# cover_pcb_2.net
KiCad netlist of a schematic drawn in EAGLE
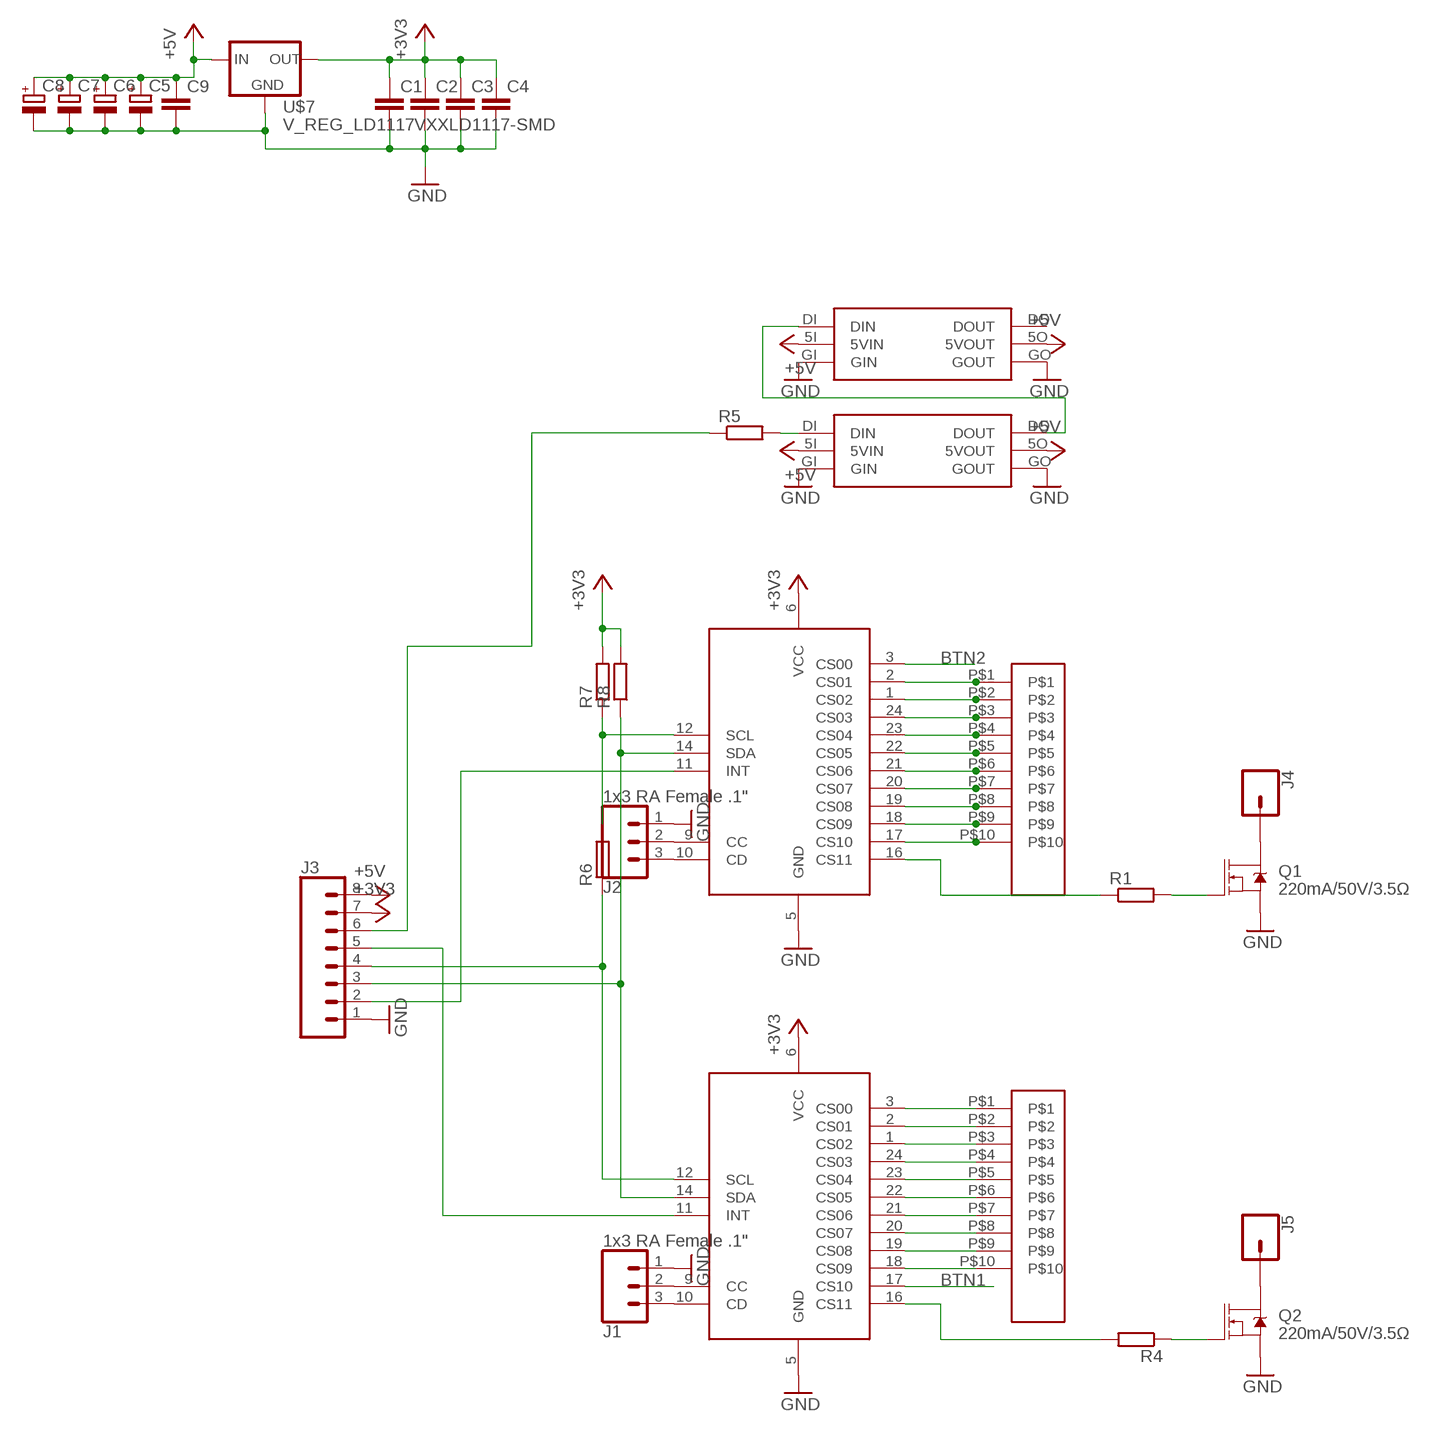
[diagram p0: schematic, sheet 1]
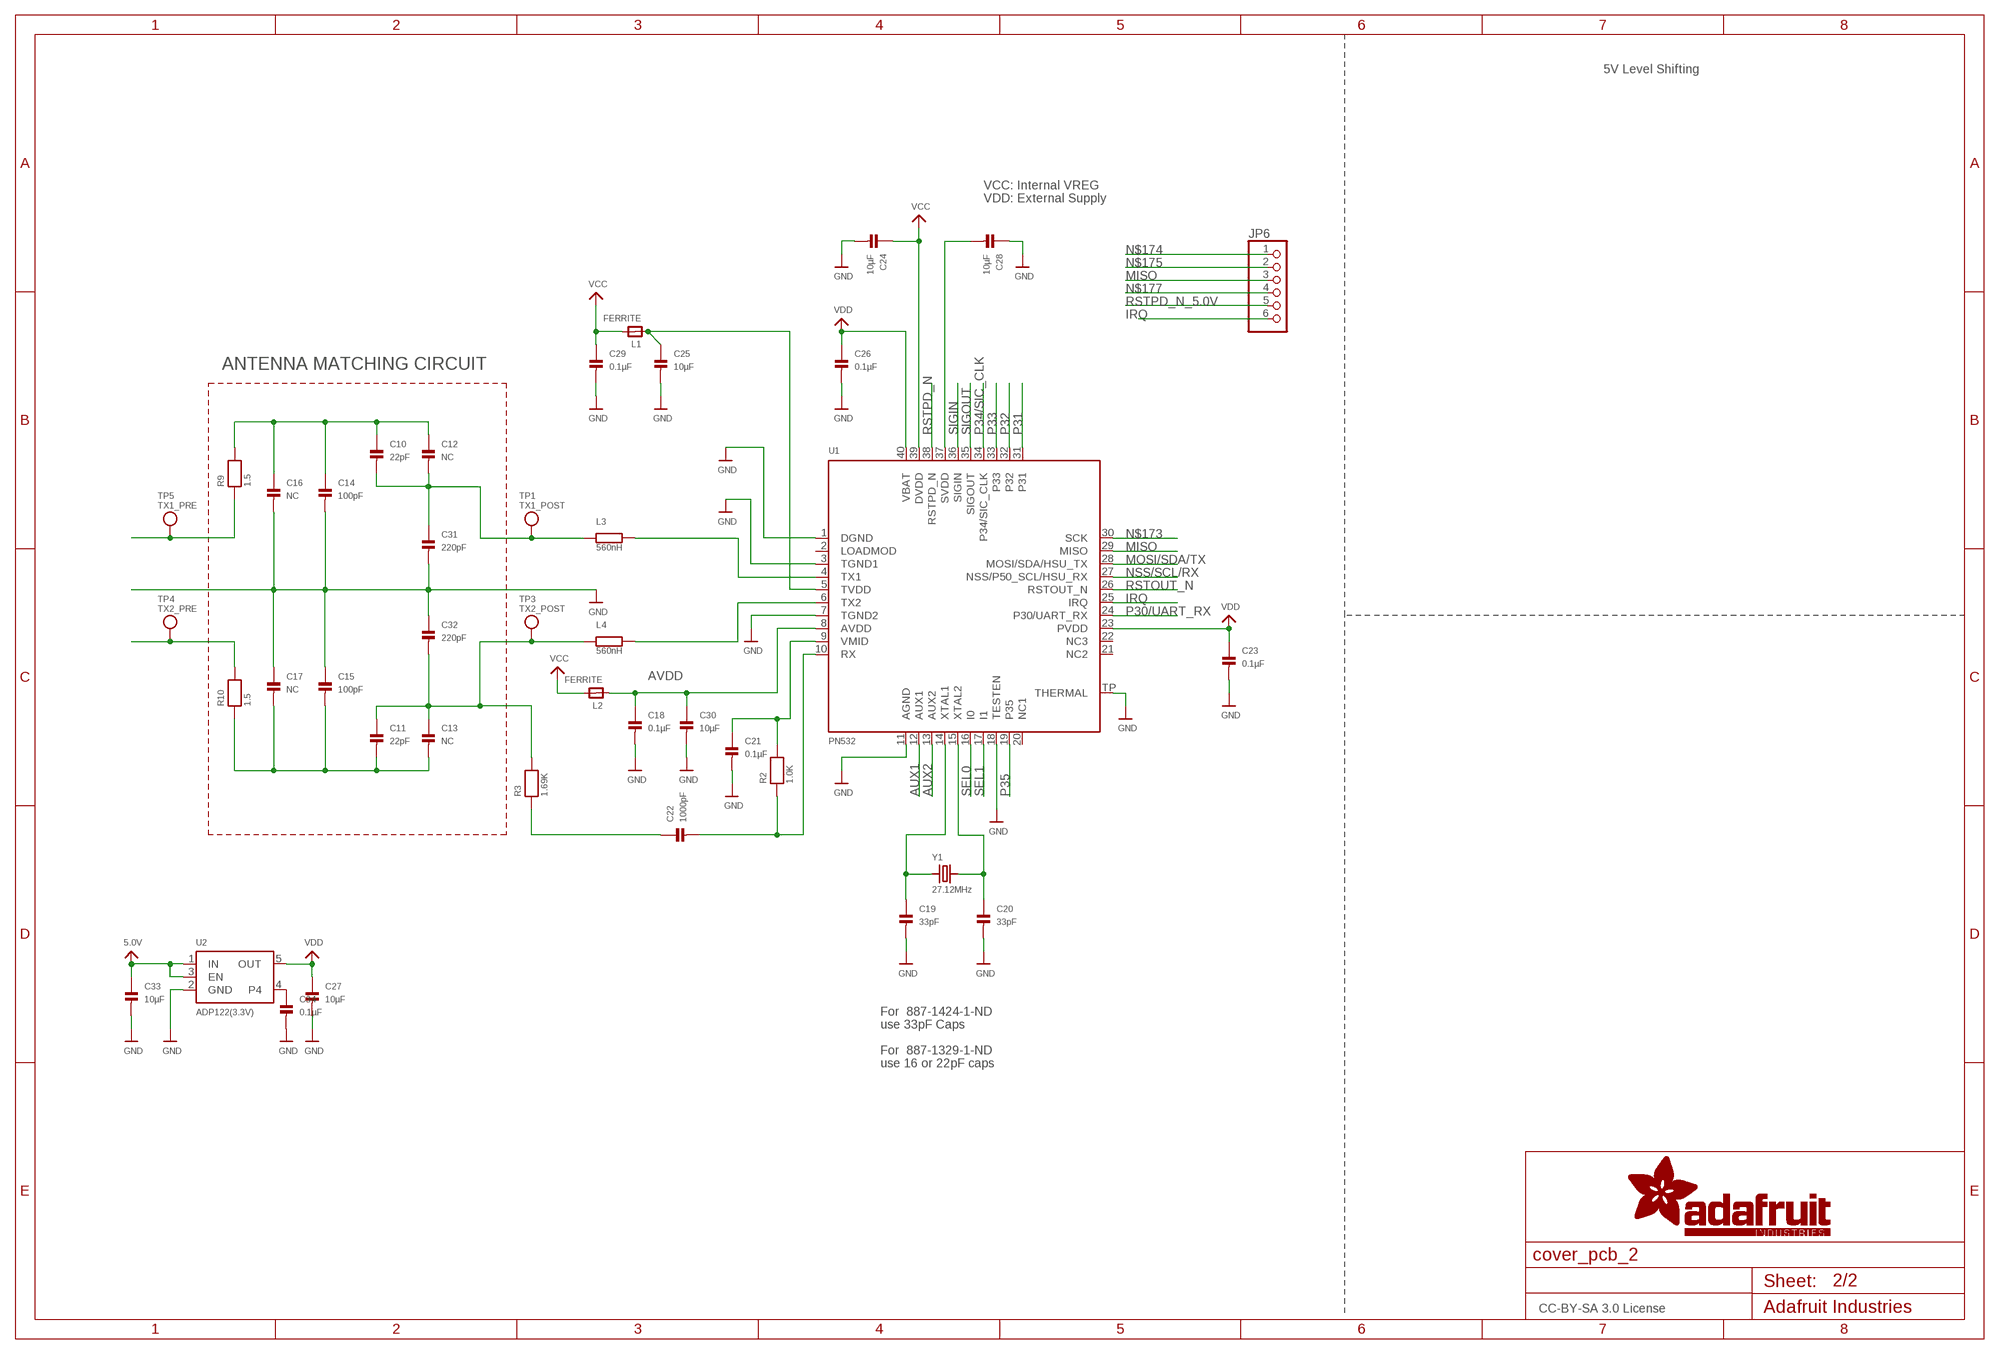
[diagram p1: schematic, sheet 2]

(export (version "E")
  (design (tool "Eeschema 10.0.6"))
  (components
    (comp (ref "C10")
      (value "22pF")
      (footprint "eagle-import:0805")
      (libsource (lib "eagle-import") (part "CAP_CERAMIC0805"))
    )
    (comp (ref "C11")
      (value "22pF")
      (footprint "eagle-import:0805")
      (libsource (lib "eagle-import") (part "CAP_CERAMIC0805"))
    )
    (comp (ref "C12")
      (value "NC")
      (footprint "eagle-import:0805")
      (libsource (lib "eagle-import") (part "CAP_CERAMIC0805"))
    )
    (comp (ref "C13")
      (value "NC")
      (footprint "eagle-import:0805")
      (libsource (lib "eagle-import") (part "CAP_CERAMIC0805"))
    )
    (comp (ref "C14")
      (value "100pF")
      (footprint "eagle-import:0805")
      (libsource (lib "eagle-import") (part "CAP_CERAMIC0805"))
    )
    (comp (ref "C15")
      (value "100pF")
      (footprint "eagle-import:0805")
      (libsource (lib "eagle-import") (part "CAP_CERAMIC0805"))
    )
    (comp (ref "C16")
      (value "NC")
      (footprint "eagle-import:0805")
      (libsource (lib "eagle-import") (part "CAP_CERAMIC0805"))
    )
    (comp (ref "C17")
      (value "NC")
      (footprint "eagle-import:0805")
      (libsource (lib "eagle-import") (part "CAP_CERAMIC0805"))
    )
    (comp (ref "C18")
      (value "0.1µF")
      (footprint "eagle-import:0805")
      (libsource (lib "eagle-import") (part "CAP_CERAMIC0805"))
    )
    (comp (ref "C19")
      (value "33pF")
      (footprint "eagle-import:0805")
      (libsource (lib "eagle-import") (part "CAP_CERAMIC0805"))
    )
    (comp (ref "C20")
      (value "33pF")
      (footprint "eagle-import:0805")
      (libsource (lib "eagle-import") (part "CAP_CERAMIC0805"))
    )
    (comp (ref "C21")
      (value "0.1µF")
      (footprint "eagle-import:0805")
      (libsource (lib "eagle-import") (part "CAP_CERAMIC0805"))
    )
    (comp (ref "C22")
      (value "1000pF")
      (footprint "eagle-import:0805")
      (libsource (lib "eagle-import") (part "CAP_CERAMIC0805"))
    )
    (comp (ref "C23")
      (value "0.1µF")
      (footprint "eagle-import:0805")
      (libsource (lib "eagle-import") (part "CAP_CERAMIC0805"))
    )
    (comp (ref "C24")
      (value "10µF")
      (footprint "eagle-import:0805")
      (libsource (lib "eagle-import") (part "CAP_CERAMIC0805"))
    )
    (comp (ref "C25")
      (value "10µF")
      (footprint "eagle-import:0805")
      (libsource (lib "eagle-import") (part "CAP_CERAMIC0805"))
    )
    (comp (ref "C26")
      (value "0.1µF")
      (footprint "eagle-import:0805")
      (libsource (lib "eagle-import") (part "CAP_CERAMIC0805"))
    )
    (comp (ref "C27")
      (value "10µF")
      (footprint "eagle-import:0805")
      (libsource (lib "eagle-import") (part "CAP_CERAMIC0805"))
    )
    (comp (ref "C28")
      (value "10µF")
      (footprint "eagle-import:0805")
      (libsource (lib "eagle-import") (part "CAP_CERAMIC0805"))
    )
    (comp (ref "C29")
      (value "0.1µF")
      (footprint "eagle-import:0805")
      (libsource (lib "eagle-import") (part "CAP_CERAMIC0805"))
    )
    (comp (ref "C30")
      (value "10µF")
      (footprint "eagle-import:0805")
      (libsource (lib "eagle-import") (part "CAP_CERAMIC0805"))
    )
    (comp (ref "C31")
      (value "220pF")
      (footprint "eagle-import:0805")
      (libsource (lib "eagle-import") (part "CAP_CERAMIC0805"))
    )
    (comp (ref "C32")
      (value "220pF")
      (footprint "eagle-import:0805")
      (libsource (lib "eagle-import") (part "CAP_CERAMIC0805"))
    )
    (comp (ref "C33")
      (value "10µF")
      (footprint "eagle-import:0805")
      (libsource (lib "eagle-import") (part "CAP_CERAMIC0805"))
    )
    (comp (ref "C34")
      (value "0.1µF")
      (footprint "eagle-import:0805")
      (libsource (lib "eagle-import") (part "CAP_CERAMIC0805"))
    )
    (comp (ref "JP6")
      (value "PINHD-1X6B")
      (footprint "eagle-import:1X06-BIG")
      (libsource (lib "eagle-import") (part "PINHD-1X6B"))
    )
    (comp (ref "L1")
      (value "FERRITE")
      (footprint "eagle-import:0805")
      (libsource (lib "eagle-import") (part "FERRITE0805"))
    )
    (comp (ref "L2")
      (value "FERRITE")
      (footprint "eagle-import:0805")
      (libsource (lib "eagle-import") (part "FERRITE0805"))
    )
    (comp (ref "L3")
      (value "560nH")
      (footprint "eagle-import:R1206")
      (libsource (lib "eagle-import") (part "R-EU_R1206"))
    )
    (comp (ref "L4")
      (value "560nH")
      (footprint "eagle-import:R1206")
      (libsource (lib "eagle-import") (part "R-EU_R1206"))
    )
    (comp (ref "R2")
      (value "1.0K")
      (footprint "eagle-import:0805")
      (libsource (lib "eagle-import") (part "RESISTOR0805"))
    )
    (comp (ref "R3")
      (value "1.69K")
      (footprint "eagle-import:0805")
      (libsource (lib "eagle-import") (part "RESISTOR0805"))
    )
    (comp (ref "R9")
      (value "1.5")
      (footprint "eagle-import:0805")
      (libsource (lib "eagle-import") (part "RESISTOR0805"))
    )
    (comp (ref "R10")
      (value "1.5")
      (footprint "eagle-import:0805")
      (libsource (lib "eagle-import") (part "RESISTOR0805"))
    )
    (comp (ref "TP1")
      (value "TX1_POST")
      (footprint "eagle-import:TESTPOINT_PAD_2MM")
      (libsource (lib "eagle-import") (part "TESTPOINTPAD"))
    )
    (comp (ref "TP3")
      (value "TX2_POST")
      (footprint "eagle-import:TESTPOINT_PAD_2MM")
      (libsource (lib "eagle-import") (part "TESTPOINTPAD"))
    )
    (comp (ref "TP4")
      (value "TX2_PRE")
      (footprint "eagle-import:TESTPOINT_PAD_2MM")
      (libsource (lib "eagle-import") (part "TESTPOINTPAD"))
    )
    (comp (ref "TP5")
      (value "TX1_PRE")
      (footprint "eagle-import:TESTPOINT_PAD_2MM")
      (libsource (lib "eagle-import") (part "TESTPOINTPAD"))
    )
    (comp (ref "U1")
      (value "PN532")
      (footprint "eagle-import:HVQFN40-6X6")
      (libsource (lib "eagle-import") (part "PN532"))
    )
    (comp (ref "U2")
      (value "ADP122(3.3V)")
      (footprint "eagle-import:SOT23-5")
      (libsource (lib "eagle-import") (part "VREG_SOT23-5"))
    )
    (comp (ref "Y1")
      (value "27.12MHz")
      (footprint "eagle-import:CRYSTAL_3.2X2.5")
      (libsource (lib "eagle-import") (part "CRYSTAL3.2X2.5"))
    )
    (comp (ref "C1")
      (value "C-EUC0805K")
      (footprint "eagle-import:C0805K")
      (libsource (lib "eagle-import") (part "C-EUC0805K"))
    )
    (comp (ref "C2")
      (value "C-EUC0805K")
      (footprint "eagle-import:C0805K")
      (libsource (lib "eagle-import") (part "C-EUC0805K"))
    )
    (comp (ref "C3")
      (value "C-EUC0805K")
      (footprint "eagle-import:C0805K")
      (libsource (lib "eagle-import") (part "C-EUC0805K"))
    )
    (comp (ref "C4")
      (value "C-EUC0805K")
      (footprint "eagle-import:C0805K")
      (libsource (lib "eagle-import") (part "C-EUC0805K"))
    )
    (comp (ref "C5")
      (value "CPOL-EUSMCD")
      (footprint "eagle-import:SMC_D")
      (libsource (lib "eagle-import") (part "CPOL-EUSMCD"))
    )
    (comp (ref "C6")
      (value "CPOL-EUSMCD")
      (footprint "eagle-import:SMC_D")
      (libsource (lib "eagle-import") (part "CPOL-EUSMCD"))
    )
    (comp (ref "C7")
      (value "CPOL-EUSMCD")
      (footprint "eagle-import:SMC_D")
      (libsource (lib "eagle-import") (part "CPOL-EUSMCD"))
    )
    (comp (ref "C8")
      (value "CPOL-EUSMCD")
      (footprint "eagle-import:SMC_D")
      (libsource (lib "eagle-import") (part "CPOL-EUSMCD"))
    )
    (comp (ref "C9")
      (value "C-EUC0805K")
      (footprint "eagle-import:C0805K")
      (libsource (lib "eagle-import") (part "C-EUC0805K"))
    )
    (comp (ref "J1")
      (value "1x3 RA Female .1\"")
      (footprint "eagle-import:1X03_SMD_RA_FEMALE")
      (libsource (lib "eagle-import") (part "CONN_03SMD_RA_FEMALE"))
    )
    (comp (ref "J2")
      (value "1x3 RA Female .1\"")
      (footprint "eagle-import:1X03_SMD_RA_FEMALE")
      (libsource (lib "eagle-import") (part "CONN_03SMD_RA_FEMALE"))
    )
    (comp (ref "J3")
      (value "CONN_08SMD-MALE")
      (footprint "eagle-import:1X08_SMD_MALE")
      (libsource (lib "eagle-import") (part "CONN_08SMD-MALE"))
    )
    (comp (ref "J4")
      (value "CONN_01SPRING-CONN")
      (footprint "eagle-import:SPRING-CONNECTOR")
      (libsource (lib "eagle-import") (part "CONN_01SPRING-CONN"))
    )
    (comp (ref "J5")
      (value "CONN_01SPRING-CONN")
      (footprint "eagle-import:SPRING-CONNECTOR")
      (libsource (lib "eagle-import") (part "CONN_01SPRING-CONN"))
    )
    (comp (ref "Q1")
      (value "220mA/50V/3.5Ω")
      (footprint "eagle-import:SOT23-3")
      (libsource (lib "eagle-import") (part "MOSFET-NCH-BSS138"))
    )
    (comp (ref "Q2")
      (value "220mA/50V/3.5Ω")
      (footprint "eagle-import:SOT23-3")
      (libsource (lib "eagle-import") (part "MOSFET-NCH-BSS138"))
    )
    (comp (ref "R1")
      (value "R-EU_R0805")
      (footprint "eagle-import:R0805")
      (libsource (lib "eagle-import") (part "R-EU_R0805"))
    )
    (comp (ref "R4")
      (value "R-EU_R0805")
      (footprint "eagle-import:R0805")
      (libsource (lib "eagle-import") (part "R-EU_R0805"))
    )
    (comp (ref "R5")
      (value "R-EU_R0805")
      (footprint "eagle-import:R0805")
      (libsource (lib "eagle-import") (part "R-EU_R0805"))
    )
    (comp (ref "R6")
      (value "R-EU_R0805")
      (footprint "eagle-import:R0805")
      (libsource (lib "eagle-import") (part "R-EU_R0805"))
    )
    (comp (ref "R7")
      (value "R-EU_R0805")
      (footprint "eagle-import:R0805")
      (libsource (lib "eagle-import") (part "R-EU_R0805"))
    )
    (comp (ref "R8")
      (value "R-EU_R0805")
      (footprint "eagle-import:R0805")
      (libsource (lib "eagle-import") (part "R-EU_R0805"))
    )
    (comp (ref "U$1")
      (value "RGB6LED")
      (footprint "eagle-import:RGB6LED")
      (libsource (lib "eagle-import") (part "RGB6LED"))
    )
    (comp (ref "U$2")
      (value "RGB6LED")
      (footprint "eagle-import:RGB6LED")
      (libsource (lib "eagle-import") (part "RGB6LED"))
    )
    (comp (ref "U$3")
      (value "TOUCH10")
      (footprint "eagle-import:TOUCH10CM")
      (libsource (lib "eagle-import") (part "TOUCH10"))
    )
    (comp (ref "U$4")
      (value "TOUCH10")
      (footprint "eagle-import:TOUCH10CM")
      (libsource (lib "eagle-import") (part "TOUCH10"))
    )
    (comp (ref "U$5")
      (value "CP112S")
      (footprint "eagle-import:QSOP24")
      (libsource (lib "eagle-import") (part "CP112S"))
    )
    (comp (ref "U$6")
      (value "CP112S")
      (footprint "eagle-import:QSOP24")
      (libsource (lib "eagle-import") (part "CP112S"))
    )
    (comp (ref "U$7")
      (value "V_REG_LD1117VXXLD1117-SMD")
      (footprint "eagle-import:SOT223")
      (libsource (lib "eagle-import") (part "V_REG_LD1117VXXLD1117-SMD"))
    )
  )
  (nets
    (net (code "1") (name "+3V3") (class "Default")
      (node (ref "C1") (pin "1") (pinfunction "1_1") (pintype "passive"))
      (node (ref "C2") (pin "1") (pinfunction "1_1") (pintype "passive"))
      (node (ref "C3") (pin "1") (pinfunction "1_1") (pintype "passive"))
      (node (ref "C4") (pin "1") (pinfunction "1_1") (pintype "passive"))
      (node (ref "J3") (pin "7") (pinfunction "7_7") (pintype "passive"))
      (node (ref "R7") (pin "2") (pinfunction "2_2") (pintype "passive"))
      (node (ref "R8") (pin "2") (pinfunction "2_2") (pintype "passive"))
      (node (ref "U$5") (pin "6") (pinfunction "VCC_6") (pintype "bidirectional"))
      (node (ref "U$6") (pin "6") (pinfunction "VCC_6") (pintype "bidirectional"))
      (node (ref "U$7") (pin "2") (pinfunction "OUT_2") (pintype "passive"))
    )
    (net (code "2") (name "+5V") (class "Default")
      (node (ref "C5") (pin "+") (pinfunction "+_+") (pintype "passive"))
      (node (ref "C6") (pin "+") (pinfunction "+_+") (pintype "passive"))
      (node (ref "C7") (pin "+") (pinfunction "+_+") (pintype "passive"))
      (node (ref "C8") (pin "+") (pinfunction "+_+") (pintype "passive"))
      (node (ref "C9") (pin "1") (pinfunction "1_1") (pintype "passive"))
      (node (ref "J3") (pin "8") (pinfunction "8_8") (pintype "passive"))
      (node (ref "U$1") (pin "5I") (pinfunction "5VIN_5I") (pintype "bidirectional"))
      (node (ref "U$1") (pin "5O") (pinfunction "5VOUT_5O") (pintype "bidirectional"))
      (node (ref "U$2") (pin "5I") (pinfunction "5VIN_5I") (pintype "bidirectional"))
      (node (ref "U$2") (pin "5O") (pinfunction "5VOUT_5O") (pintype "bidirectional"))
      (node (ref "U$7") (pin "3") (pinfunction "IN_3") (pintype "input"))
    )
    (net (code "3") (name "5.0V") (class "Default")
      (node (ref "C33") (pin "1") (pinfunction "P$1_1") (pintype "passive"))
      (node (ref "U2") (pin "1") (pinfunction "IN_1") (pintype "bidirectional"))
      (node (ref "U2") (pin "3") (pinfunction "EN_3") (pintype "bidirectional"))
    )
    (net (code "4") (name "AUX1") (class "Default")
      (node (ref "U1") (pin "12") (pinfunction "AUX1_12") (pintype "bidirectional"))
    )
    (net (code "5") (name "AUX2") (class "Default")
      (node (ref "U1") (pin "13") (pinfunction "AUX2_13") (pintype "bidirectional"))
    )
    (net (code "6") (name "AVDD") (class "Default")
      (node (ref "C18") (pin "1") (pinfunction "P$1_1") (pintype "passive"))
      (node (ref "C30") (pin "1") (pinfunction "P$1_1") (pintype "passive"))
      (node (ref "L2") (pin "1") (pinfunction "P$1_1") (pintype "passive"))
      (node (ref "U1") (pin "8") (pinfunction "AVDD_8") (pintype "bidirectional"))
    )
    (net (code "7") (name "BTN1") (class "Default")
      (node (ref "U$6") (pin "17") (pinfunction "CS10_17") (pintype "bidirectional"))
    )
    (net (code "8") (name "BTN2") (class "Default")
      (node (ref "U$5") (pin "3") (pinfunction "CS00_3") (pintype "bidirectional"))
    )
    (net (code "9") (name "GND") (class "Default")
      (node (ref "C1") (pin "2") (pinfunction "2_2") (pintype "passive"))
      (node (ref "C14") (pin "2") (pinfunction "P$2_2") (pintype "passive"))
      (node (ref "C15") (pin "1") (pinfunction "P$1_1") (pintype "passive"))
      (node (ref "C16") (pin "2") (pinfunction "P$2_2") (pintype "passive"))
      (node (ref "C17") (pin "1") (pinfunction "P$1_1") (pintype "passive"))
      (node (ref "C18") (pin "2") (pinfunction "P$2_2") (pintype "passive"))
      (node (ref "C19") (pin "2") (pinfunction "P$2_2") (pintype "passive"))
      (node (ref "C2") (pin "2") (pinfunction "2_2") (pintype "passive"))
      (node (ref "C20") (pin "2") (pinfunction "P$2_2") (pintype "passive"))
      (node (ref "C21") (pin "2") (pinfunction "P$2_2") (pintype "passive"))
      (node (ref "C23") (pin "2") (pinfunction "P$2_2") (pintype "passive"))
      (node (ref "C24") (pin "2") (pinfunction "P$2_2") (pintype "passive"))
      (node (ref "C25") (pin "2") (pinfunction "P$2_2") (pintype "passive"))
      (node (ref "C26") (pin "2") (pinfunction "P$2_2") (pintype "passive"))
      (node (ref "C27") (pin "2") (pinfunction "P$2_2") (pintype "passive"))
      (node (ref "C28") (pin "1") (pinfunction "P$1_1") (pintype "passive"))
      (node (ref "C29") (pin "2") (pinfunction "P$2_2") (pintype "passive"))
      (node (ref "C3") (pin "2") (pinfunction "2_2") (pintype "passive"))
      (node (ref "C30") (pin "2") (pinfunction "P$2_2") (pintype "passive"))
      (node (ref "C31") (pin "2") (pinfunction "P$2_2") (pintype "passive"))
      (node (ref "C32") (pin "1") (pinfunction "P$1_1") (pintype "passive"))
      (node (ref "C33") (pin "2") (pinfunction "P$2_2") (pintype "passive"))
      (node (ref "C34") (pin "2") (pinfunction "P$2_2") (pintype "passive"))
      (node (ref "C4") (pin "2") (pinfunction "2_2") (pintype "passive"))
      (node (ref "C5") (pin "-") (pinfunction "-_-") (pintype "passive"))
      (node (ref "C6") (pin "-") (pinfunction "-_-") (pintype "passive"))
      (node (ref "C7") (pin "-") (pinfunction "-_-") (pintype "passive"))
      (node (ref "C8") (pin "-") (pinfunction "-_-") (pintype "passive"))
      (node (ref "C9") (pin "2") (pinfunction "2_2") (pintype "passive"))
      (node (ref "J1") (pin "1") (pinfunction "1_1") (pintype "passive"))
      (node (ref "J2") (pin "1") (pinfunction "1_1") (pintype "passive"))
      (node (ref "J3") (pin "1") (pinfunction "1_1") (pintype "passive"))
      (node (ref "Q1") (pin "2") (pinfunction "S_2") (pintype "bidirectional"))
      (node (ref "Q2") (pin "2") (pinfunction "S_2") (pintype "bidirectional"))
      (node (ref "U$1") (pin "GI") (pinfunction "GIN_GI") (pintype "bidirectional"))
      (node (ref "U$1") (pin "GO") (pinfunction "GOUT_GO") (pintype "bidirectional"))
      (node (ref "U$2") (pin "GI") (pinfunction "GIN_GI") (pintype "bidirectional"))
      (node (ref "U$2") (pin "GO") (pinfunction "GOUT_GO") (pintype "bidirectional"))
      (node (ref "U$5") (pin "5") (pinfunction "GND_5") (pintype "bidirectional"))
      (node (ref "U$6") (pin "5") (pinfunction "GND_5") (pintype "bidirectional"))
      (node (ref "U$7") (pin "1") (pinfunction "GND_1") (pintype "input"))
      (node (ref "U1") (pin "1") (pinfunction "DGND_1") (pintype "bidirectional"))
      (node (ref "U1") (pin "11") (pinfunction "AGND_11") (pintype "bidirectional"))
      (node (ref "U1") (pin "18") (pinfunction "TESTEN_18") (pintype "bidirectional"))
      (node (ref "U1") (pin "3") (pinfunction "TGND1_3") (pintype "bidirectional"))
      (node (ref "U1") (pin "7") (pinfunction "TGND2_7") (pintype "bidirectional"))
      (node (ref "U1") (pin "TP") (pinfunction "THERMAL_TP") (pintype "bidirectional"))
      (node (ref "U2") (pin "2") (pinfunction "GND_2") (pintype "bidirectional"))
    )
    (net (code "10") (name "IRQ") (class "Default")
      (node (ref "JP6") (pin "6") (pinfunction "6_6") (pintype "passive"))
      (node (ref "U1") (pin "25") (pinfunction "IRQ_25") (pintype "bidirectional"))
    )
    (net (code "11") (name "MISO") (class "Default")
      (node (ref "JP6") (pin "3") (pinfunction "3_3") (pintype "passive"))
      (node (ref "U1") (pin "29") (pinfunction "MISO_29") (pintype "bidirectional"))
    )
    (net (code "12") (name "MOSI{slash}SDA{slash}TX") (class "Default")
      (node (ref "U1") (pin "28") (pinfunction "MOSI/SDA/HSU_TX_28") (pintype "bidirectional"))
    )
    (net (code "13") (name "N$173") (class "Default")
      (node (ref "U1") (pin "30") (pinfunction "SCK_30") (pintype "bidirectional"))
    )
    (net (code "14") (name "N$174") (class "Default")
      (node (ref "JP6") (pin "1") (pinfunction "1_1") (pintype "passive"))
    )
    (net (code "15") (name "N$175") (class "Default")
      (node (ref "JP6") (pin "2") (pinfunction "2_2") (pintype "passive"))
    )
    (net (code "16") (name "N$177") (class "Default")
      (node (ref "JP6") (pin "4") (pinfunction "4_4") (pintype "passive"))
    )
    (net (code "17") (name "NSS{slash}SCL{slash}RX") (class "Default")
      (node (ref "U1") (pin "27") (pinfunction "NSS/P50_SCL/HSU_RX_27") (pintype "bidirectional"))
    )
    (net (code "18") (name "Net-(C10-P$1)") (class "Default")
      (node (ref "C10") (pin "1") (pinfunction "P$1_1") (pintype "passive"))
      (node (ref "C12") (pin "1") (pinfunction "P$1_1") (pintype "passive"))
      (node (ref "C14") (pin "1") (pinfunction "P$1_1") (pintype "passive"))
      (node (ref "C16") (pin "1") (pinfunction "P$1_1") (pintype "passive"))
      (node (ref "R9") (pin "2") (pinfunction "2_2") (pintype "passive"))
    )
    (net (code "19") (name "Net-(C10-P$2)") (class "Default")
      (node (ref "C10") (pin "2") (pinfunction "P$2_2") (pintype "passive"))
      (node (ref "C12") (pin "2") (pinfunction "P$2_2") (pintype "passive"))
      (node (ref "C31") (pin "1") (pinfunction "P$1_1") (pintype "passive"))
      (node (ref "L3") (pin "1") (pinfunction "1_1") (pintype "passive"))
      (node (ref "TP1") (pin "P$1") (pinfunction "P$1_P$1") (pintype "bidirectional"))
    )
    (net (code "20") (name "Net-(C11-P$1)") (class "Default")
      (node (ref "C11") (pin "1") (pinfunction "P$1_1") (pintype "passive"))
      (node (ref "C13") (pin "1") (pinfunction "P$1_1") (pintype "passive"))
      (node (ref "C32") (pin "2") (pinfunction "P$2_2") (pintype "passive"))
      (node (ref "L4") (pin "1") (pinfunction "1_1") (pintype "passive"))
      (node (ref "R3") (pin "2") (pinfunction "2_2") (pintype "passive"))
      (node (ref "TP3") (pin "P$1") (pinfunction "P$1_P$1") (pintype "bidirectional"))
    )
    (net (code "21") (name "Net-(C11-P$2)") (class "Default")
      (node (ref "C11") (pin "2") (pinfunction "P$2_2") (pintype "passive"))
      (node (ref "C13") (pin "2") (pinfunction "P$2_2") (pintype "passive"))
      (node (ref "C15") (pin "2") (pinfunction "P$2_2") (pintype "passive"))
      (node (ref "C17") (pin "2") (pinfunction "P$2_2") (pintype "passive"))
      (node (ref "R10") (pin "1") (pinfunction "1_1") (pintype "passive"))
    )
    (net (code "22") (name "Net-(C19-P$1)") (class "Default")
      (node (ref "C19") (pin "1") (pinfunction "P$1_1") (pintype "passive"))
      (node (ref "U1") (pin "14") (pinfunction "XTAL1_14") (pintype "bidirectional"))
      (node (ref "Y1") (pin "1") (pinfunction "1_1") (pintype "passive"))
    )
    (net (code "23") (name "Net-(C20-P$1)") (class "Default")
      (node (ref "C20") (pin "1") (pinfunction "P$1_1") (pintype "passive"))
      (node (ref "U1") (pin "15") (pinfunction "XTAL2_15") (pintype "bidirectional"))
      (node (ref "Y1") (pin "2") (pinfunction "2_2") (pintype "passive"))
    )
    (net (code "24") (name "Net-(C21-P$1)") (class "Default")
      (node (ref "C21") (pin "1") (pinfunction "P$1_1") (pintype "passive"))
      (node (ref "R2") (pin "2") (pinfunction "2_2") (pintype "passive"))
      (node (ref "U1") (pin "9") (pinfunction "VMID_9") (pintype "bidirectional"))
    )
    (net (code "25") (name "Net-(C22-P$1)") (class "Default")
      (node (ref "C22") (pin "1") (pinfunction "P$1_1") (pintype "passive"))
      (node (ref "R3") (pin "1") (pinfunction "1_1") (pintype "passive"))
    )
    (net (code "26") (name "Net-(C22-P$2)") (class "Default")
      (node (ref "C22") (pin "2") (pinfunction "P$2_2") (pintype "passive"))
      (node (ref "R2") (pin "1") (pinfunction "1_1") (pintype "passive"))
      (node (ref "U1") (pin "10") (pinfunction "RX_10") (pintype "bidirectional"))
    )
    (net (code "27") (name "Net-(C25-P$1)") (class "Default")
      (node (ref "C25") (pin "1") (pinfunction "P$1_1") (pintype "passive"))
      (node (ref "L1") (pin "1") (pinfunction "P$1_1") (pintype "passive"))
      (node (ref "U1") (pin "5") (pinfunction "TVDD_5") (pintype "bidirectional"))
    )
    (net (code "28") (name "Net-(C28-P$2)") (class "Default")
      (node (ref "C28") (pin "2") (pinfunction "P$2_2") (pintype "passive"))
      (node (ref "U1") (pin "37") (pinfunction "SVDD_37") (pintype "bidirectional"))
    )
    (net (code "29") (name "Net-(C34-P$1)") (class "Default")
      (node (ref "C34") (pin "1") (pinfunction "P$1_1") (pintype "passive"))
      (node (ref "U2") (pin "4") (pinfunction "P4_4") (pintype "bidirectional"))
    )
    (net (code "30") (name "Net-(J3-Pad6)") (class "Default")
      (node (ref "J3") (pin "6") (pinfunction "6_6") (pintype "passive"))
      (node (ref "R5") (pin "1") (pinfunction "1_1") (pintype "passive"))
    )
    (net (code "31") (name "Net-(J4-1)") (class "Default")
      (node (ref "J4") (pin "P$2") (pinfunction "1_P$2") (pintype "passive"))
      (node (ref "Q1") (pin "3") (pinfunction "D_3") (pintype "bidirectional"))
    )
    (net (code "32") (name "Net-(J5-1)") (class "Default")
      (node (ref "J5") (pin "P$2") (pinfunction "1_P$2") (pintype "passive"))
      (node (ref "Q2") (pin "3") (pinfunction "D_3") (pintype "bidirectional"))
    )
    (net (code "33") (name "Net-(Q1-G)") (class "Default")
      (node (ref "Q1") (pin "1") (pinfunction "G_1") (pintype "bidirectional"))
      (node (ref "R1") (pin "2") (pinfunction "2_2") (pintype "passive"))
    )
    (net (code "34") (name "Net-(Q2-G)") (class "Default")
      (node (ref "Q2") (pin "1") (pinfunction "G_1") (pintype "bidirectional"))
      (node (ref "R4") (pin "1") (pinfunction "1_1") (pintype "passive"))
    )
    (net (code "35") (name "Net-(R9-Pad1)") (class "Default")
      (node (ref "R9") (pin "1") (pinfunction "1_1") (pintype "passive"))
      (node (ref "TP5") (pin "P$1") (pinfunction "P$1_P$1") (pintype "bidirectional"))
    )
    (net (code "36") (name "Net-(R10-Pad2)") (class "Default")
      (node (ref "R10") (pin "2") (pinfunction "2_2") (pintype "passive"))
      (node (ref "TP4") (pin "P$1") (pinfunction "P$1_P$1") (pintype "bidirectional"))
    )
    (net (code "37") (name "Net-(U$1-DIN)") (class "Default")
      (node (ref "U$1") (pin "DI") (pinfunction "DIN_DI") (pintype "bidirectional"))
      (node (ref "U$2") (pin "DO") (pinfunction "DOUT_DO") (pintype "bidirectional"))
    )
    (net (code "38") (name "Net-(U$2-DIN)") (class "Default")
      (node (ref "R5") (pin "2") (pinfunction "2_2") (pintype "passive"))
      (node (ref "U$2") (pin "DI") (pinfunction "DIN_DI") (pintype "bidirectional"))
    )
    (net (code "39") (name "Net-(U$5-CC)") (class "Default")
      (node (ref "J2") (pin "2") (pinfunction "2_2") (pintype "passive"))
      (node (ref "U$5") (pin "9") (pinfunction "CC_9") (pintype "bidirectional"))
    )
    (net (code "40") (name "Net-(U$5-CD)") (class "Default")
      (node (ref "J2") (pin "3") (pinfunction "3_3") (pintype "passive"))
      (node (ref "U$5") (pin "10") (pinfunction "CD_10") (pintype "bidirectional"))
    )
    (net (code "41") (name "Net-(U$5-CS01)") (class "Default")
      (node (ref "U$3") (pin "P$1") (pinfunction "P$1_P$1") (pintype "bidirectional"))
      (node (ref "U$5") (pin "2") (pinfunction "CS01_2") (pintype "bidirectional"))
    )
    (net (code "42") (name "Net-(U$5-CS02)") (class "Default")
      (node (ref "U$3") (pin "P$2") (pinfunction "P$2_P$2") (pintype "bidirectional"))
      (node (ref "U$5") (pin "1") (pinfunction "CS02_1") (pintype "bidirectional"))
    )
    (net (code "43") (name "Net-(U$5-CS03)") (class "Default")
      (node (ref "U$3") (pin "P$3") (pinfunction "P$3_P$3") (pintype "bidirectional"))
      (node (ref "U$5") (pin "24") (pinfunction "CS03_24") (pintype "bidirectional"))
    )
    (net (code "44") (name "Net-(U$5-CS04)") (class "Default")
      (node (ref "U$3") (pin "P$4") (pinfunction "P$4_P$4") (pintype "bidirectional"))
      (node (ref "U$5") (pin "23") (pinfunction "CS04_23") (pintype "bidirectional"))
    )
    (net (code "45") (name "Net-(U$5-CS05)") (class "Default")
      (node (ref "U$3") (pin "P$5") (pinfunction "P$5_P$5") (pintype "bidirectional"))
      (node (ref "U$5") (pin "22") (pinfunction "CS05_22") (pintype "bidirectional"))
    )
    (net (code "46") (name "Net-(U$5-CS06)") (class "Default")
      (node (ref "U$3") (pin "P$6") (pinfunction "P$6_P$6") (pintype "bidirectional"))
      (node (ref "U$5") (pin "21") (pinfunction "CS06_21") (pintype "bidirectional"))
    )
    (net (code "47") (name "Net-(U$5-CS07)") (class "Default")
      (node (ref "U$3") (pin "P$7") (pinfunction "P$7_P$7") (pintype "bidirectional"))
      (node (ref "U$5") (pin "20") (pinfunction "CS07_20") (pintype "bidirectional"))
    )
    (net (code "48") (name "Net-(U$5-CS08)") (class "Default")
      (node (ref "U$3") (pin "P$8") (pinfunction "P$8_P$8") (pintype "bidirectional"))
      (node (ref "U$5") (pin "19") (pinfunction "CS08_19") (pintype "bidirectional"))
    )
    (net (code "49") (name "Net-(U$5-CS09)") (class "Default")
      (node (ref "U$3") (pin "P$9") (pinfunction "P$9_P$9") (pintype "bidirectional"))
      (node (ref "U$5") (pin "18") (pinfunction "CS09_18") (pintype "bidirectional"))
    )
    (net (code "50") (name "Net-(U$5-CS10)") (class "Default")
      (node (ref "U$3") (pin "P$10") (pinfunction "P$10_P$10") (pintype "bidirectional"))
      (node (ref "U$5") (pin "17") (pinfunction "CS10_17") (pintype "bidirectional"))
    )
    (net (code "51") (name "Net-(U$5-CS11)") (class "Default")
      (node (ref "R1") (pin "1") (pinfunction "1_1") (pintype "passive"))
      (node (ref "U$5") (pin "16") (pinfunction "CS11_16") (pintype "bidirectional"))
    )
    (net (code "52") (name "Net-(U$5-INT)") (class "Default")
      (node (ref "J3") (pin "2") (pinfunction "2_2") (pintype "passive"))
      (node (ref "U$5") (pin "11") (pinfunction "INT_11") (pintype "bidirectional"))
    )
    (net (code "53") (name "Net-(U$5-SCL)") (class "Default")
      (node (ref "R6") (pin "2") (pinfunction "2_2") (pintype "passive"))
      (node (ref "R7") (pin "1") (pinfunction "1_1") (pintype "passive"))
      (node (ref "U$5") (pin "12") (pinfunction "SCL_12") (pintype "bidirectional"))
    )
    (net (code "54") (name "Net-(U$5-SDA)") (class "Default")
      (node (ref "J3") (pin "3") (pinfunction "3_3") (pintype "passive"))
      (node (ref "R8") (pin "1") (pinfunction "1_1") (pintype "passive"))
      (node (ref "U$5") (pin "14") (pinfunction "SDA_14") (pintype "bidirectional"))
      (node (ref "U$6") (pin "14") (pinfunction "SDA_14") (pintype "bidirectional"))
    )
    (net (code "55") (name "Net-(U$6-CC)") (class "Default")
      (node (ref "J1") (pin "2") (pinfunction "2_2") (pintype "passive"))
      (node (ref "U$6") (pin "9") (pinfunction "CC_9") (pintype "bidirectional"))
    )
    (net (code "56") (name "Net-(U$6-CD)") (class "Default")
      (node (ref "J1") (pin "3") (pinfunction "3_3") (pintype "passive"))
      (node (ref "U$6") (pin "10") (pinfunction "CD_10") (pintype "bidirectional"))
    )
    (net (code "57") (name "Net-(U$6-CS00)") (class "Default")
      (node (ref "U$4") (pin "P$1") (pinfunction "P$1_P$1") (pintype "bidirectional"))
      (node (ref "U$6") (pin "3") (pinfunction "CS00_3") (pintype "bidirectional"))
    )
    (net (code "58") (name "Net-(U$6-CS01)") (class "Default")
      (node (ref "U$4") (pin "P$2") (pinfunction "P$2_P$2") (pintype "bidirectional"))
      (node (ref "U$6") (pin "2") (pinfunction "CS01_2") (pintype "bidirectional"))
    )
    (net (code "59") (name "Net-(U$6-CS02)") (class "Default")
      (node (ref "U$4") (pin "P$3") (pinfunction "P$3_P$3") (pintype "bidirectional"))
      (node (ref "U$6") (pin "1") (pinfunction "CS02_1") (pintype "bidirectional"))
    )
    (net (code "60") (name "Net-(U$6-CS03)") (class "Default")
      (node (ref "U$4") (pin "P$4") (pinfunction "P$4_P$4") (pintype "bidirectional"))
      (node (ref "U$6") (pin "24") (pinfunction "CS03_24") (pintype "bidirectional"))
    )
    (net (code "61") (name "Net-(U$6-CS04)") (class "Default")
      (node (ref "U$4") (pin "P$5") (pinfunction "P$5_P$5") (pintype "bidirectional"))
      (node (ref "U$6") (pin "23") (pinfunction "CS04_23") (pintype "bidirectional"))
    )
    (net (code "62") (name "Net-(U$6-CS05)") (class "Default")
      (node (ref "U$4") (pin "P$6") (pinfunction "P$6_P$6") (pintype "bidirectional"))
      (node (ref "U$6") (pin "22") (pinfunction "CS05_22") (pintype "bidirectional"))
    )
    (net (code "63") (name "Net-(U$6-CS06)") (class "Default")
      (node (ref "U$4") (pin "P$7") (pinfunction "P$7_P$7") (pintype "bidirectional"))
      (node (ref "U$6") (pin "21") (pinfunction "CS06_21") (pintype "bidirectional"))
    )
    (net (code "64") (name "Net-(U$6-CS07)") (class "Default")
      (node (ref "U$4") (pin "P$8") (pinfunction "P$8_P$8") (pintype "bidirectional"))
      (node (ref "U$6") (pin "20") (pinfunction "CS07_20") (pintype "bidirectional"))
    )
    (net (code "65") (name "Net-(U$6-CS08)") (class "Default")
      (node (ref "U$4") (pin "P$9") (pinfunction "P$9_P$9") (pintype "bidirectional"))
      (node (ref "U$6") (pin "19") (pinfunction "CS08_19") (pintype "bidirectional"))
    )
    (net (code "66") (name "Net-(U$6-CS09)") (class "Default")
      (node (ref "U$4") (pin "P$10") (pinfunction "P$10_P$10") (pintype "bidirectional"))
      (node (ref "U$6") (pin "18") (pinfunction "CS09_18") (pintype "bidirectional"))
    )
    (net (code "67") (name "Net-(U$6-CS11)") (class "Default")
      (node (ref "R4") (pin "2") (pinfunction "2_2") (pintype "passive"))
      (node (ref "U$6") (pin "16") (pinfunction "CS11_16") (pintype "bidirectional"))
    )
    (net (code "68") (name "Net-(U$6-INT)") (class "Default")
      (node (ref "J3") (pin "5") (pinfunction "5_5") (pintype "passive"))
      (node (ref "U$6") (pin "11") (pinfunction "INT_11") (pintype "bidirectional"))
    )
    (net (code "69") (name "Net-(U$6-SCL)") (class "Default")
      (node (ref "J3") (pin "4") (pinfunction "4_4") (pintype "passive"))
      (node (ref "R6") (pin "1") (pinfunction "1_1") (pintype "passive"))
      (node (ref "U$6") (pin "12") (pinfunction "SCL_12") (pintype "bidirectional"))
    )
    (net (code "70") (name "Net-(U1-TX1)") (class "Default")
      (node (ref "L3") (pin "2") (pinfunction "2_2") (pintype "passive"))
      (node (ref "U1") (pin "4") (pinfunction "TX1_4") (pintype "bidirectional"))
    )
    (net (code "71") (name "Net-(U1-TX2)") (class "Default")
      (node (ref "L4") (pin "2") (pinfunction "2_2") (pintype "passive"))
      (node (ref "U1") (pin "6") (pinfunction "TX2_6") (pintype "bidirectional"))
    )
    (net (code "72") (name "P30{slash}UART_RX") (class "Default")
      (node (ref "U1") (pin "24") (pinfunction "P30/UART_RX_24") (pintype "bidirectional"))
    )
    (net (code "73") (name "P31") (class "Default")
      (node (ref "U1") (pin "31") (pinfunction "P31_31") (pintype "bidirectional"))
    )
    (net (code "74") (name "P32") (class "Default")
      (node (ref "U1") (pin "32") (pinfunction "P32_32") (pintype "bidirectional"))
    )
    (net (code "75") (name "P33") (class "Default")
      (node (ref "U1") (pin "33") (pinfunction "P33_33") (pintype "bidirectional"))
    )
    (net (code "76") (name "P34{slash}SIC_CLK") (class "Default")
      (node (ref "U1") (pin "34") (pinfunction "P34/SIC_CLK_34") (pintype "bidirectional"))
    )
    (net (code "77") (name "P35") (class "Default")
      (node (ref "U1") (pin "19") (pinfunction "P35_19") (pintype "bidirectional"))
    )
    (net (code "78") (name "RSTOUT_N") (class "Default")
      (node (ref "U1") (pin "26") (pinfunction "RSTOUT_N_26") (pintype "bidirectional"))
    )
    (net (code "79") (name "RSTPD_N") (class "Default")
      (node (ref "U1") (pin "38") (pinfunction "RSTPD_N_38") (pintype "bidirectional"))
    )
    (net (code "80") (name "RSTPD_N_5.0V") (class "Default")
      (node (ref "JP6") (pin "5") (pinfunction "5_5") (pintype "passive"))
    )
    (net (code "81") (name "SEL0") (class "Default")
      (node (ref "U1") (pin "16") (pinfunction "I0_16") (pintype "bidirectional"))
    )
    (net (code "82") (name "SEL1") (class "Default")
      (node (ref "U1") (pin "17") (pinfunction "I1_17") (pintype "bidirectional"))
    )
    (net (code "83") (name "SIGIN") (class "Default")
      (node (ref "U1") (pin "36") (pinfunction "SIGIN_36") (pintype "bidirectional"))
    )
    (net (code "84") (name "SIGOUT") (class "Default")
      (node (ref "U1") (pin "35") (pinfunction "SIGOUT_35") (pintype "bidirectional"))
    )
    (net (code "85") (name "VCC") (class "Default")
      (node (ref "C24") (pin "1") (pinfunction "P$1_1") (pintype "passive"))
      (node (ref "C29") (pin "1") (pinfunction "P$1_1") (pintype "passive"))
      (node (ref "L1") (pin "2") (pinfunction "P$2_2") (pintype "passive"))
      (node (ref "L2") (pin "2") (pinfunction "P$2_2") (pintype "passive"))
      (node (ref "U1") (pin "39") (pinfunction "DVDD_39") (pintype "bidirectional"))
    )
    (net (code "86") (name "VDD") (class "Default")
      (node (ref "C23") (pin "1") (pinfunction "P$1_1") (pintype "passive"))
      (node (ref "C26") (pin "1") (pinfunction "P$1_1") (pintype "passive"))
      (node (ref "C27") (pin "1") (pinfunction "P$1_1") (pintype "passive"))
      (node (ref "U1") (pin "23") (pinfunction "PVDD_23") (pintype "bidirectional"))
      (node (ref "U1") (pin "40") (pinfunction "VBAT_40") (pintype "bidirectional"))
      (node (ref "U2") (pin "5") (pinfunction "OUT_5") (pintype "bidirectional"))
    )
    (net (code "87") (name "unconnected-(U$1-DOUT-PadDO)") (class "Default")
      (node (ref "U$1") (pin "DO") (pinfunction "DOUT_DO") (pintype "bidirectional"))
    )
    (net (code "88") (name "unconnected-(U1-LOADMOD-Pad2)") (class "Default")
      (node (ref "U1") (pin "2") (pinfunction "LOADMOD_2") (pintype "bidirectional"))
    )
    (net (code "89") (name "unconnected-(U1-NC1-Pad20)") (class "Default")
      (node (ref "U1") (pin "20") (pinfunction "NC1_20") (pintype "bidirectional"))
    )
    (net (code "90") (name "unconnected-(U1-NC2-Pad21)") (class "Default")
      (node (ref "U1") (pin "21") (pinfunction "NC2_21") (pintype "bidirectional"))
    )
    (net (code "91") (name "unconnected-(U1-NC3-Pad22)") (class "Default")
      (node (ref "U1") (pin "22") (pinfunction "NC3_22") (pintype "bidirectional"))
    )
  )
)
